# POWER.net
KiCad netlist of a schematic drawn in Altium Designer
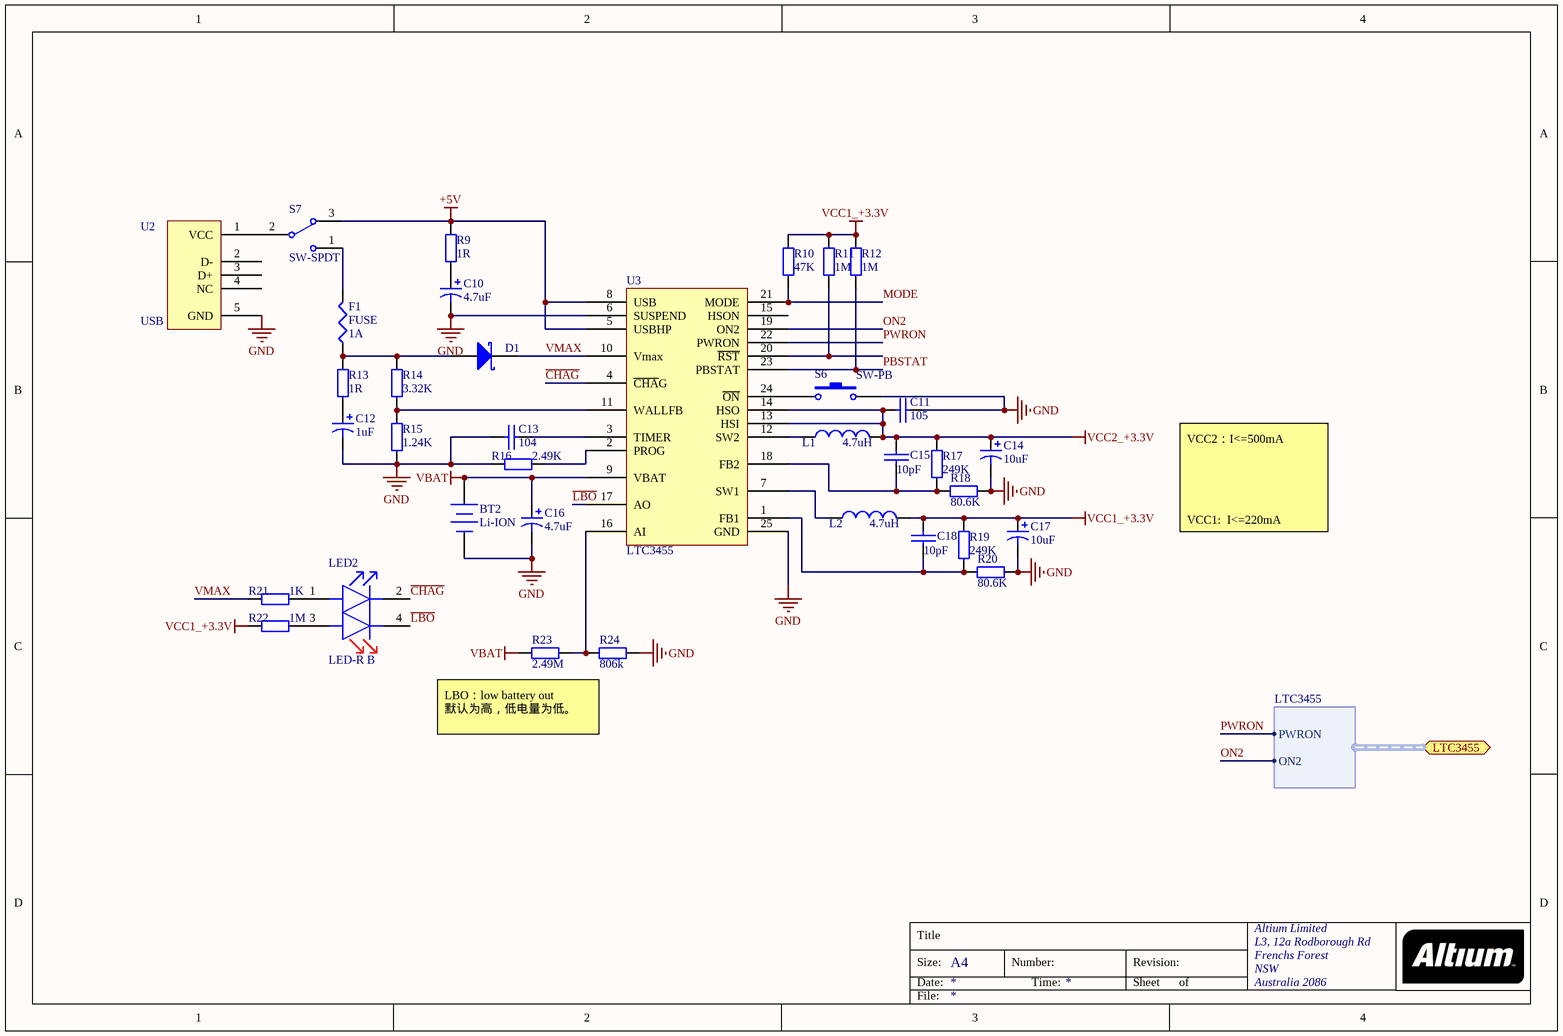
[diagram p0: POWER.SchDoc]

(export (version "E")
  (design (tool "Eeschema 10.0.6"))
  (components
    (comp (ref "BT2")
      (value "Li-ION")
      (footprint "BAT-2")
      (description "Multicell Battery")
      (fields (field (name "PUBLISHER") "Altium Limited"))
      (libsource (lib "Miscellaneous Devices") (part "Battery"))
    )
    (comp (ref "C10")
      (value "4.7uF")
      (footprint "SMA-C")
      (description "Polarized Capacitor (Radial)")
      (fields (field (name "Comment") "Cap Pol1") (field (name "PUBLISHER") "Altium Limited"))
      (libsource (lib "Miscellaneous Devices") (part "Cap Pol1"))
    )
    (comp (ref "C11")
      (value "105")
      (footprint "C0805")
      (description "Capacitor")
      (libsource (lib "*") (part "CAP"))
    )
    (comp (ref "C12")
      (value "1uF")
      (footprint "C0805")
      (description "Polarized Capacitor (Radial)")
      (fields (field (name "Comment") "Cap Pol1") (field (name "PUBLISHER") "Altium Limited"))
      (libsource (lib "Miscellaneous Devices") (part "Cap Pol1"))
    )
    (comp (ref "C13")
      (value "104")
      (footprint "C0805")
      (description "Capacitor")
      (libsource (lib "*") (part "CAP"))
    )
    (comp (ref "C14")
      (value "10uF")
      (footprint "SMA-C")
      (description "Polarized Capacitor (Radial)")
      (fields (field (name "Comment") "Cap Pol1") (field (name "PUBLISHER") "Altium Limited"))
      (libsource (lib "Miscellaneous Devices") (part "Cap Pol1"))
    )
    (comp (ref "C15")
      (value "10pF")
      (footprint "C0805")
      (description "Capacitor")
      (libsource (lib "*") (part "CAP"))
    )
    (comp (ref "C16")
      (value "4.7uF")
      (footprint "SMA-C")
      (description "Polarized Capacitor (Radial)")
      (fields (field (name "Comment") "Cap Pol1") (field (name "PUBLISHER") "Altium Limited"))
      (libsource (lib "Miscellaneous Devices") (part "Cap Pol1"))
    )
    (comp (ref "C17")
      (value "10uF")
      (footprint "SMA-C")
      (description "Polarized Capacitor (Radial)")
      (fields (field (name "Comment") "Cap Pol1") (field (name "PUBLISHER") "Altium Limited"))
      (libsource (lib "Miscellaneous Devices") (part "Cap Pol1"))
    )
    (comp (ref "C18")
      (value "10pF")
      (footprint "C0805")
      (description "Capacitor")
      (libsource (lib "*") (part "CAP"))
    )
    (comp (ref "D1")
      (value "MBR120")
      (footprint "DO-214AB")
      (description "Schottky Diode")
      (fields (field (name "PUBLISHER") "Altium Limited"))
      (libsource (lib "xxxlzjxxx Devices") (part "D Schottky"))
    )
    (comp (ref "F1")
      (value "FUSE")
      (footprint "R1812")
      (description "Resistor")
      (fields (field (name "ALTIUM_VALUE") "1A") (field (name "PUBLISHER") "Altium Limited"))
      (libsource (lib "xxxlzjxxx Devices") (part "Res3"))
    )
    (comp (ref "L1")
      (value "4.7uH")
      (footprint "L-5X4mm-S")
      (description "Inductor")
      (fields (field (name "PUBLISHER") "Altium Limited"))
      (libsource (lib "Miscellaneous Devices") (part "Inductor"))
    )
    (comp (ref "L2")
      (value "4.7uH")
      (footprint "L-5X4mm-S")
      (description "Inductor")
      (fields (field (name "PUBLISHER") "Altium Limited"))
      (libsource (lib "Miscellaneous Devices") (part "Inductor"))
    )
    (comp (ref "LED2")
      (value "LED-R B")
      (footprint "0805LED - r b")
      (libsource (lib "FR5969v1.0") (part "LED-R B"))
    )
    (comp (ref "R9")
      (value "1R")
      (footprint "R0805")
      (description "Resistor")
      (fields (field (name "Comment") "Res2") (field (name "PUBLISHER") "Altium Limited"))
      (libsource (lib "Miscellaneous Devices") (part "Res2"))
    )
    (comp (ref "R10")
      (value "47K")
      (footprint "R0805")
      (description "Resistor")
      (fields (field (name "Comment") "Res2") (field (name "PUBLISHER") "Altium Limited"))
      (libsource (lib "Miscellaneous Devices") (part "Res2"))
    )
    (comp (ref "R11")
      (value "1M")
      (footprint "R0805")
      (description "Resistor")
      (fields (field (name "Comment") "Res2") (field (name "PUBLISHER") "Altium Limited"))
      (libsource (lib "Miscellaneous Devices") (part "Res2"))
    )
    (comp (ref "R12")
      (value "1M")
      (footprint "R0805")
      (description "Resistor")
      (fields (field (name "Comment") "Res2") (field (name "PUBLISHER") "Altium Limited"))
      (libsource (lib "Miscellaneous Devices") (part "Res2"))
    )
    (comp (ref "R13")
      (value "1R")
      (footprint "R0805")
      (description "Resistor")
      (fields (field (name "Comment") "Res2") (field (name "PUBLISHER") "Altium Limited"))
      (libsource (lib "Miscellaneous Devices") (part "Res2"))
    )
    (comp (ref "R14")
      (value "3.32K")
      (footprint "R0805")
      (description "Resistor")
      (fields (field (name "Comment") "Res2") (field (name "PUBLISHER") "Altium Limited"))
      (libsource (lib "Miscellaneous Devices") (part "Res2"))
    )
    (comp (ref "R15")
      (value "1.24K")
      (footprint "R0805")
      (description "Resistor")
      (fields (field (name "Comment") "Res2") (field (name "PUBLISHER") "Altium Limited"))
      (libsource (lib "") (part "Res2_3"))
    )
    (comp (ref "R16")
      (value "2.49K")
      (footprint "R0805")
      (description "Resistor")
      (fields (field (name "Comment") "Res2") (field (name "PUBLISHER") "Altium Limited"))
      (libsource (lib "") (part "Res2_2"))
    )
    (comp (ref "R17")
      (value "249K")
      (footprint "R0805")
      (description "Resistor")
      (fields (field (name "Comment") "Res2") (field (name "PUBLISHER") "Altium Limited"))
      (libsource (lib "Miscellaneous Devices") (part "Res2"))
    )
    (comp (ref "R18")
      (value "80.6K")
      (footprint "R0805")
      (description "Resistor")
      (fields (field (name "Comment") "Res2") (field (name "PUBLISHER") "Altium Limited"))
      (libsource (lib "") (part "Res2_1"))
    )
    (comp (ref "R19")
      (value "249K")
      (footprint "R0805")
      (description "Resistor")
      (fields (field (name "Comment") "Res2") (field (name "PUBLISHER") "Altium Limited"))
      (libsource (lib "Miscellaneous Devices") (part "Res2"))
    )
    (comp (ref "R20")
      (value "80.6K")
      (footprint "R0805")
      (description "Resistor")
      (fields (field (name "Comment") "Res2") (field (name "PUBLISHER") "Altium Limited"))
      (libsource (lib "") (part "Res2_1"))
    )
    (comp (ref "R21")
      (value "1K")
      (footprint "R0805")
      (description "Resistor")
      (fields (field (name "Comment") "Res2") (field (name "PUBLISHER") "Altium Limited"))
      (libsource (lib "") (part "Res2_1"))
    )
    (comp (ref "R22")
      (value "1M")
      (footprint "R0805")
      (description "Resistor")
      (fields (field (name "Comment") "Res2") (field (name "PUBLISHER") "Altium Limited"))
      (libsource (lib "") (part "Res2_2"))
    )
    (comp (ref "R23")
      (value "2.49M")
      (footprint "R0805")
      (description "Resistor")
      (fields (field (name "Comment") "Res2") (field (name "PUBLISHER") "Altium Limited"))
      (libsource (lib "") (part "Res2_1"))
    )
    (comp (ref "R24")
      (value "806k")
      (footprint "R0805")
      (description "Resistor")
      (fields (field (name "Comment") "Res2") (field (name "PUBLISHER") "Altium Limited"))
      (libsource (lib "") (part "Res2_1"))
    )
    (comp (ref "S6")
      (value "SW-PB")
      (footprint "SW-SMD1")
      (description "Switch")
      (fields (field (name "PUBLISHER") "Altium Limited"))
      (libsource (lib "Miscellaneous Devices") (part "SW-PB"))
    )
    (comp (ref "S7")
      (value "SW-SPDT")
      (footprint "HDR1X3")
      (description "SPDT Subminiature Toggle Switch, Right Angle Mounting, Vertical Actuation")
      (fields (field (name "PUBLISHER") "Altium Limited"))
      (libsource (lib "xxxlzjxxx Devices") (part "SW-SPDT"))
    )
    (comp (ref "U2") (value "USB") (footprint "USB-mini") (libsource (lib "STM32F030xxxx") (part "USB")))
    (comp (ref "U3")
      (value "LTC3455")
      (footprint "QFN-24")
      (description "LI-CELL charger")
      (libsource (lib "FR5969v1.0") (part "LTC3455"))
    )
  )
  (nets
    (net (code "2") (name "+5V") (class "Default")
      (node (ref "R9") (pin "2") (pinfunction "2_2") (pintype "passive"))
      (node (ref "S7") (pin "3") (pinfunction "3_3") (pintype "passive"))
      (node (ref "U3") (pin "5") (pinfunction "USBHP_5") (pintype "passive"))
      (node (ref "U3") (pin "8") (pinfunction "USB_8") (pintype "passive"))
    )
    (net (code "3") (name "/MODE") (class "Default")
      (node (ref "R10") (pin "1") (pinfunction "1_1") (pintype "passive"))
      (node (ref "U3") (pin "21") (pinfunction "MODE_21") (pintype "passive"))
    )
    (net (code "4") (name "/ON2") (class "Default")
      (node (ref "U3") (pin "19") (pinfunction "ON2_19") (pintype "passive"))
    )
    (net (code "5") (name "/PBSTAT") (class "Default")
      (node (ref "R12") (pin "1") (pinfunction "1_1") (pintype "passive"))
      (node (ref "U3") (pin "23") (pinfunction "PBSTAT_23") (pintype "passive"))
    )
    (net (code "6") (name "/PWRON") (class "Default")
      (node (ref "U3") (pin "22") (pinfunction "PWRON_22") (pintype "passive"))
    )
    (net (code "7") (name "/VMAX") (class "Default")
      (node (ref "D1") (pin "2") (pinfunction "K_2") (pintype "passive"))
      (node (ref "R21") (pin "2") (pinfunction "2_2") (pintype "passive"))
      (node (ref "U3") (pin "10") (pinfunction "Vmax_10") (pintype "passive"))
    )
    (net (code "9") (name "/~{CHAG}") (class "Default")
      (node (ref "LED2") (pin "2") (pinfunction "2_2") (pintype "passive"))
      (node (ref "U3") (pin "4") (pinfunction "~{CHA}G_4") (pintype "passive"))
    )
    (net (code "10") (name "/~{LBO}") (class "Default")
      (node (ref "LED2") (pin "4") (pinfunction "4_4") (pintype "passive"))
      (node (ref "U3") (pin "17") (pinfunction "AO_17") (pintype "passive"))
    )
    (net (code "11") (name "GND") (class "Default")
      (node (ref "BT2") (pin "2") (pinfunction "-_2") (pintype "passive"))
      (node (ref "C10") (pin "2") (pinfunction "2_2") (pintype "passive"))
      (node (ref "C11") (pin "1") (pinfunction "1_1") (pintype "passive"))
      (node (ref "C12") (pin "2") (pinfunction "2_2") (pintype "passive"))
      (node (ref "C13") (pin "2") (pinfunction "2_2") (pintype "passive"))
      (node (ref "C14") (pin "2") (pinfunction "2_2") (pintype "passive"))
      (node (ref "C16") (pin "2") (pinfunction "2_2") (pintype "passive"))
      (node (ref "C17") (pin "2") (pinfunction "2_2") (pintype "passive"))
      (node (ref "R15") (pin "2") (pinfunction "2_2") (pintype "passive"))
      (node (ref "R16") (pin "1") (pinfunction "1_1") (pintype "passive"))
      (node (ref "R18") (pin "1") (pinfunction "1_1") (pintype "passive"))
      (node (ref "R20") (pin "1") (pinfunction "1_1") (pintype "passive"))
      (node (ref "R24") (pin "1") (pinfunction "1_1") (pintype "passive"))
      (node (ref "S6") (pin "2") (pinfunction "2_2") (pintype "passive"))
      (node (ref "U2") (pin "5") (pinfunction "GND_5") (pintype "passive"))
      (node (ref "U3") (pin "25") (pinfunction "GND_25") (pintype "passive"))
      (node (ref "U3") (pin "6") (pinfunction "SUSPEND_6") (pintype "passive"))
    )
    (net (code "12") (name "Net-(C10-Pad1)") (class "Default")
      (node (ref "C10") (pin "1") (pinfunction "1_1") (pintype "passive"))
      (node (ref "R9") (pin "1") (pinfunction "1_1") (pintype "passive"))
    )
    (net (code "13") (name "Net-(C12-Pad1)") (class "Default")
      (node (ref "C12") (pin "1") (pinfunction "1_1") (pintype "passive"))
      (node (ref "R13") (pin "1") (pinfunction "1_1") (pintype "passive"))
    )
    (net (code "14") (name "Net-(D1-A)") (class "Default")
      (node (ref "D1") (pin "1") (pinfunction "A_1") (pintype "passive"))
      (node (ref "F1") (pin "1") (pinfunction "1_1") (pintype "passive"))
      (node (ref "R13") (pin "2") (pinfunction "2_2") (pintype "passive"))
      (node (ref "R14") (pin "2") (pinfunction "2_2") (pintype "passive"))
    )
    (net (code "15") (name "Net-(F1-Pad2)") (class "Default")
      (node (ref "F1") (pin "2") (pinfunction "2_2") (pintype "passive"))
      (node (ref "S7") (pin "1") (pinfunction "1_1") (pintype "passive"))
    )
    (net (code "16") (name "Net-(LED2-Pad1)") (class "Default")
      (node (ref "LED2") (pin "1") (pinfunction "1_1") (pintype "passive"))
      (node (ref "R21") (pin "1") (pinfunction "1_1") (pintype "passive"))
    )
    (net (code "17") (name "Net-(LED2-Pad3)") (class "Default")
      (node (ref "LED2") (pin "3") (pinfunction "3_3") (pintype "passive"))
      (node (ref "R22") (pin "2") (pinfunction "2_2") (pintype "passive"))
    )
    (net (code "18") (name "Net-(U2-VCC)") (class "Default")
      (node (ref "S7") (pin "2") (pinfunction "2_2") (pintype "passive"))
      (node (ref "U2") (pin "1") (pinfunction "VCC_1") (pintype "passive"))
    )
    (net (code "19") (name "Net-(U3-AI)") (class "Default")
      (node (ref "R23") (pin "1") (pinfunction "1_1") (pintype "passive"))
      (node (ref "R24") (pin "2") (pinfunction "2_2") (pintype "passive"))
      (node (ref "U3") (pin "16") (pinfunction "AI_16") (pintype "passive"))
    )
    (net (code "20") (name "Net-(U3-FB1)") (class "Default")
      (node (ref "C18") (pin "2") (pinfunction "2_2") (pintype "passive"))
      (node (ref "R19") (pin "1") (pinfunction "1_1") (pintype "passive"))
      (node (ref "R20") (pin "2") (pinfunction "2_2") (pintype "passive"))
      (node (ref "U3") (pin "1") (pinfunction "FB1_1") (pintype "passive"))
    )
    (net (code "21") (name "Net-(U3-FB2)") (class "Default")
      (node (ref "C15") (pin "2") (pinfunction "2_2") (pintype "passive"))
      (node (ref "R17") (pin "1") (pinfunction "1_1") (pintype "passive"))
      (node (ref "R18") (pin "2") (pinfunction "2_2") (pintype "passive"))
      (node (ref "U3") (pin "18") (pinfunction "FB2_18") (pintype "passive"))
    )
    (net (code "22") (name "Net-(U3-PROG)") (class "Default")
      (node (ref "R16") (pin "2") (pinfunction "2_2") (pintype "passive"))
      (node (ref "U3") (pin "2") (pinfunction "PROG_2") (pintype "passive"))
    )
    (net (code "23") (name "Net-(U3-SW1)") (class "Default")
      (node (ref "L2") (pin "1") (pinfunction "1_1") (pintype "passive"))
      (node (ref "U3") (pin "7") (pinfunction "SW1_7") (pintype "passive"))
    )
    (net (code "24") (name "Net-(U3-SW2)") (class "Default")
      (node (ref "L1") (pin "1") (pinfunction "1_1") (pintype "passive"))
      (node (ref "U3") (pin "12") (pinfunction "SW2_12") (pintype "passive"))
    )
    (net (code "25") (name "Net-(U3-TIMER)") (class "Default")
      (node (ref "C13") (pin "1") (pinfunction "1_1") (pintype "passive"))
      (node (ref "U3") (pin "3") (pinfunction "TIMER_3") (pintype "passive"))
    )
    (net (code "26") (name "Net-(U3-WALLFB)") (class "Default")
      (node (ref "R14") (pin "1") (pinfunction "1_1") (pintype "passive"))
      (node (ref "R15") (pin "1") (pinfunction "1_1") (pintype "passive"))
      (node (ref "U3") (pin "11") (pinfunction "WALLFB_11") (pintype "passive"))
    )
    (net (code "27") (name "Net-(U3-~{ON})") (class "Default")
      (node (ref "S6") (pin "1") (pinfunction "1_1") (pintype "passive"))
      (node (ref "U3") (pin "24") (pinfunction "~{ON}_24") (pintype "passive"))
    )
    (net (code "28") (name "Net-(U3-~{RST})") (class "Default")
      (node (ref "R11") (pin "1") (pinfunction "1_1") (pintype "passive"))
      (node (ref "U3") (pin "20") (pinfunction "~{RST}_20") (pintype "passive"))
    )
    (net (code "29") (name "VBAT") (class "Default")
      (node (ref "BT2") (pin "1") (pinfunction "+_1") (pintype "passive"))
      (node (ref "C16") (pin "1") (pinfunction "1_1") (pintype "passive"))
      (node (ref "R23") (pin "2") (pinfunction "2_2") (pintype "passive"))
      (node (ref "U3") (pin "9") (pinfunction "VBAT_9") (pintype "passive"))
    )
    (net (code "30") (name "VCC1_+3.3V") (class "Default")
      (node (ref "C17") (pin "1") (pinfunction "1_1") (pintype "passive"))
      (node (ref "C18") (pin "1") (pinfunction "1_1") (pintype "passive"))
      (node (ref "L2") (pin "2") (pinfunction "2_2") (pintype "passive"))
      (node (ref "R10") (pin "2") (pinfunction "2_2") (pintype "passive"))
      (node (ref "R11") (pin "2") (pinfunction "2_2") (pintype "passive"))
      (node (ref "R12") (pin "2") (pinfunction "2_2") (pintype "passive"))
      (node (ref "R19") (pin "2") (pinfunction "2_2") (pintype "passive"))
      (node (ref "R22") (pin "1") (pinfunction "1_1") (pintype "passive"))
    )
    (net (code "31") (name "VCC2_+3.3V") (class "Default")
      (node (ref "C11") (pin "2") (pinfunction "2_2") (pintype "passive"))
      (node (ref "C14") (pin "1") (pinfunction "1_1") (pintype "passive"))
      (node (ref "C15") (pin "1") (pinfunction "1_1") (pintype "passive"))
      (node (ref "L1") (pin "2") (pinfunction "2_2") (pintype "passive"))
      (node (ref "R17") (pin "2") (pinfunction "2_2") (pintype "passive"))
      (node (ref "U3") (pin "13") (pinfunction "HSI_13") (pintype "passive"))
      (node (ref "U3") (pin "14") (pinfunction "HSO_14") (pintype "passive"))
    )
    (net (code "32") (name "unconnected-(U2-D+-Pad3)") (class "Default")
      (node (ref "U2") (pin "3") (pinfunction "D+_3") (pintype "passive"))
    )
    (net (code "33") (name "unconnected-(U2-D--Pad2)") (class "Default")
      (node (ref "U2") (pin "2") (pinfunction "D-_2") (pintype "passive"))
    )
    (net (code "34") (name "unconnected-(U2-NC-Pad4)") (class "Default")
      (node (ref "U2") (pin "4") (pinfunction "NC_4") (pintype "passive"))
    )
    (net (code "35") (name "unconnected-(U3-HSON-Pad15)") (class "Default")
      (node (ref "U3") (pin "15") (pinfunction "HSON_15") (pintype "passive"))
    )
  )
)
